# bateria.net
KiCad netlist of a schematic drawn in EAGLE
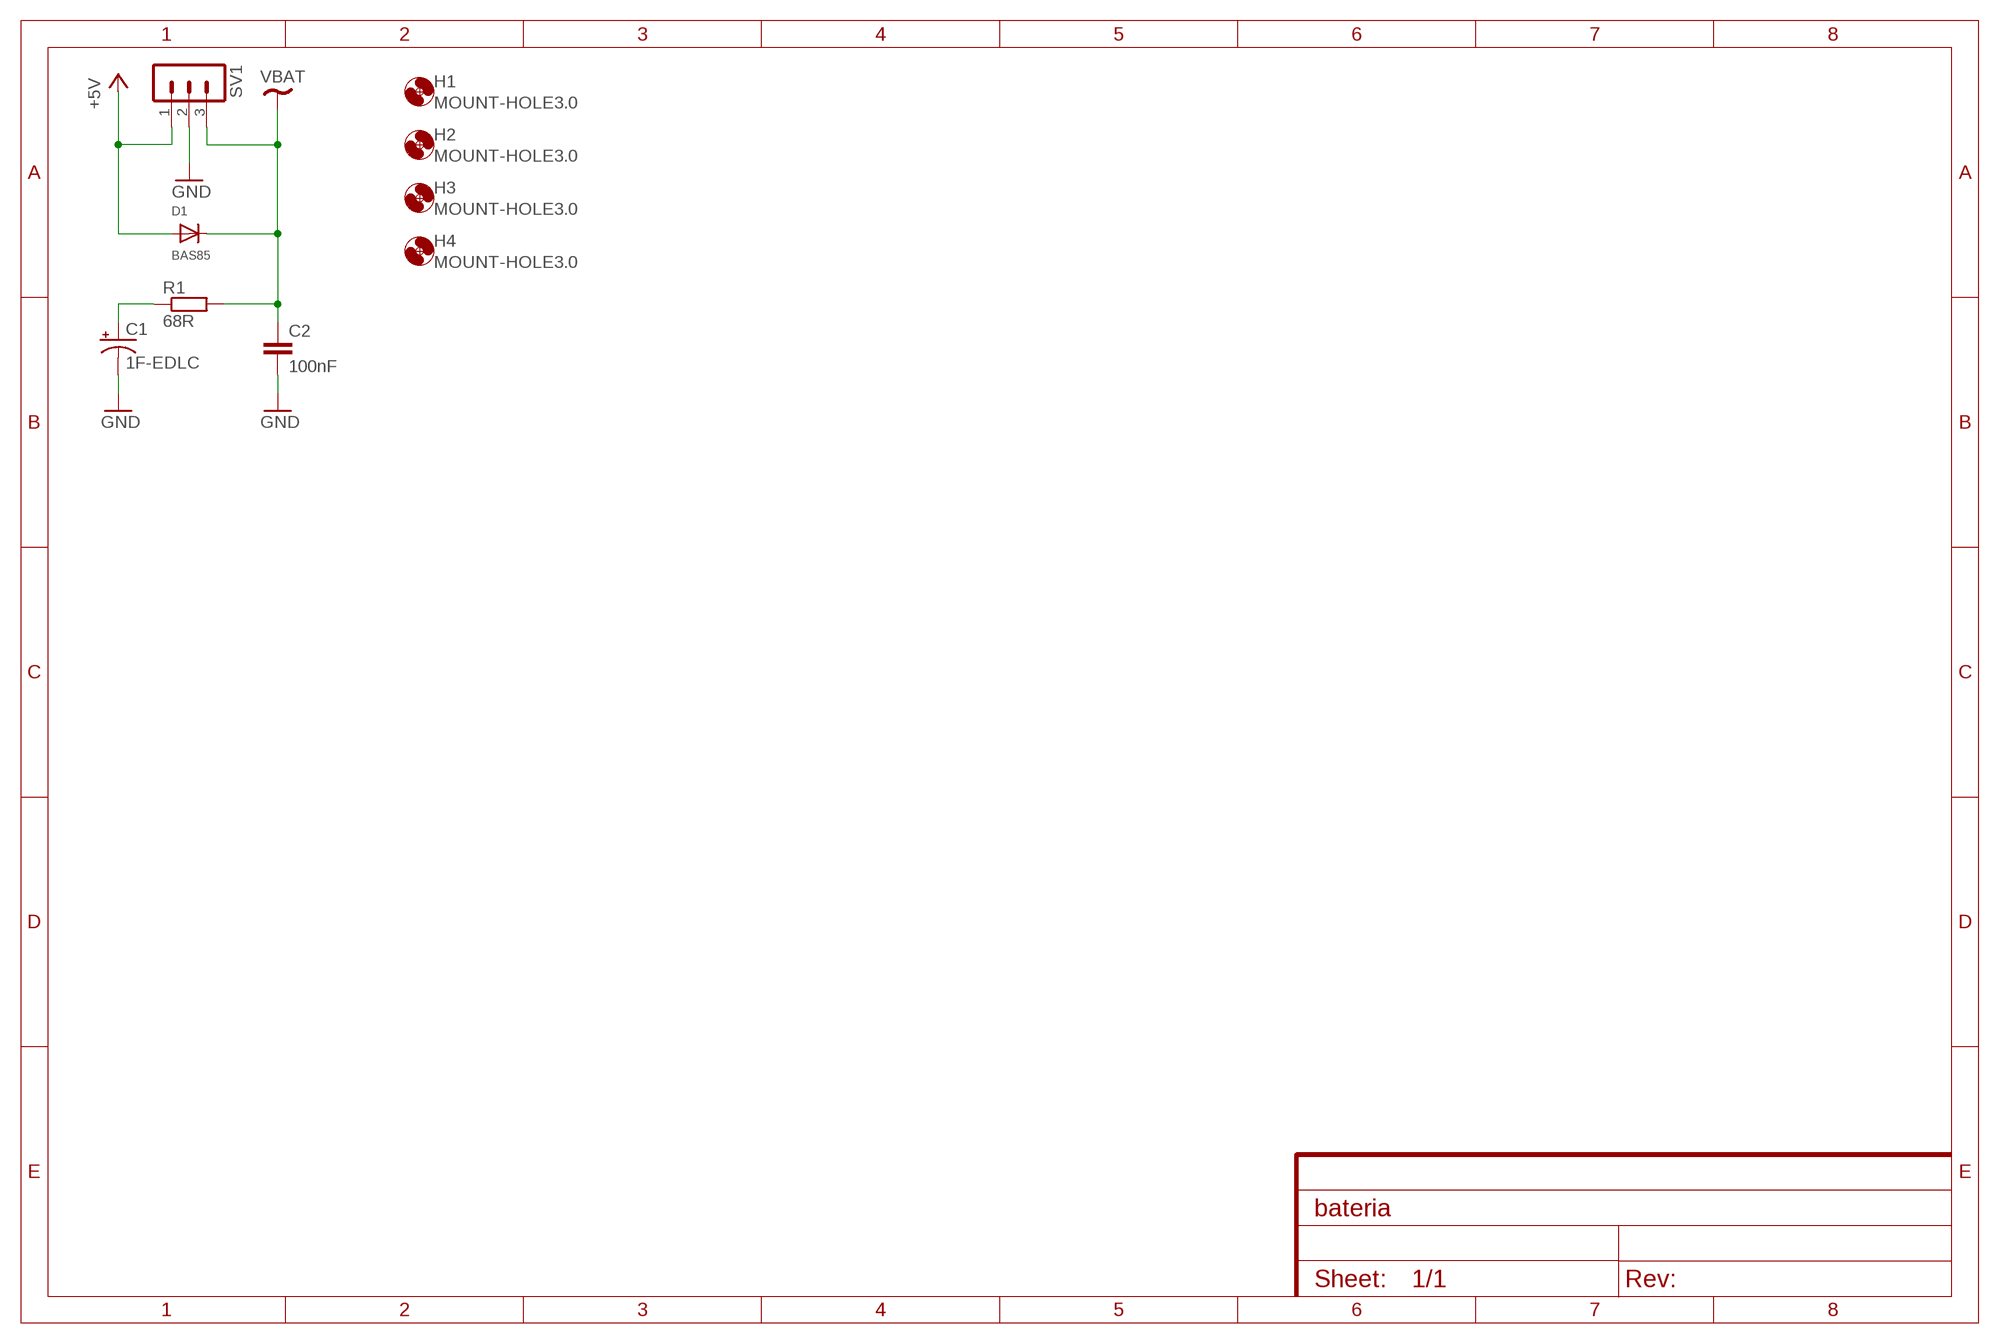
[diagram p0: schematic, sheet 1]

(export (version "E")
  (design (tool "Eeschema 10.0.6"))
  (components
    (comp (ref "C1")
      (value "1F-EDLC")
      (footprint "eagle-import:CAP-RADIAL-5MM-21.5MM")
      (libsource (lib "eagle-import") (part "1F-EDLC"))
    )
    (comp (ref "C2")
      (value "100nF")
      (footprint "eagle-import:C0805")
      (libsource (lib "eagle-import") (part "C-EUC0805"))
    )
    (comp (ref "D1")
      (value "BAS85")
      (footprint "eagle-import:SMADIODE")
      (libsource (lib "eagle-import") (part "DIODESMA"))
    )
    (comp (ref "H1")
      (value "MOUNT-HOLE3.0")
      (footprint "eagle-import:3,0")
      (libsource (lib "eagle-import") (part "MOUNT-HOLE3.0"))
    )
    (comp (ref "H2")
      (value "MOUNT-HOLE3.0")
      (footprint "eagle-import:3,0")
      (libsource (lib "eagle-import") (part "MOUNT-HOLE3.0"))
    )
    (comp (ref "H3")
      (value "MOUNT-HOLE3.0")
      (footprint "eagle-import:3,0")
      (libsource (lib "eagle-import") (part "MOUNT-HOLE3.0"))
    )
    (comp (ref "H4")
      (value "MOUNT-HOLE3.0")
      (footprint "eagle-import:3,0")
      (libsource (lib "eagle-import") (part "MOUNT-HOLE3.0"))
    )
    (comp (ref "R1")
      (value "68R")
      (footprint "eagle-import:R0805")
      (libsource (lib "eagle-import") (part "R-EU_R0805"))
    )
    (comp (ref "SV1")
      (value "MA03-1")
      (footprint "eagle-import:MA03-1")
      (libsource (lib "eagle-import") (part "MA03-1"))
    )
  )
  (nets
    (net (code "1") (name "+5V") (class "Default")
      (node (ref "D1") (pin "A") (pinfunction "A_A") (pintype "passive"))
      (node (ref "SV1") (pin "1") (pinfunction "1_1") (pintype "passive"))
    )
    (net (code "2") (name "GND") (class "Default")
      (node (ref "C1") (pin "-") (pinfunction "-_-") (pintype "passive"))
      (node (ref "C2") (pin "2") (pinfunction "2_2") (pintype "passive"))
      (node (ref "SV1") (pin "2") (pinfunction "2_2") (pintype "passive"))
    )
    (net (code "3") (name "Net-(C1-Pad+)") (class "Default")
      (node (ref "C1") (pin "+") (pinfunction "+_+") (pintype "passive"))
      (node (ref "R1") (pin "1") (pinfunction "1_1") (pintype "passive"))
    )
    (net (code "4") (name "VBAT") (class "Default")
      (node (ref "C2") (pin "1") (pinfunction "1_1") (pintype "passive"))
      (node (ref "D1") (pin "C") (pinfunction "C_C") (pintype "passive"))
      (node (ref "R1") (pin "2") (pinfunction "2_2") (pintype "passive"))
      (node (ref "SV1") (pin "3") (pinfunction "3_3") (pintype "passive"))
    )
  )
)
